# traning_shield.net
KiCad netlist of a schematic drawn in EAGLE
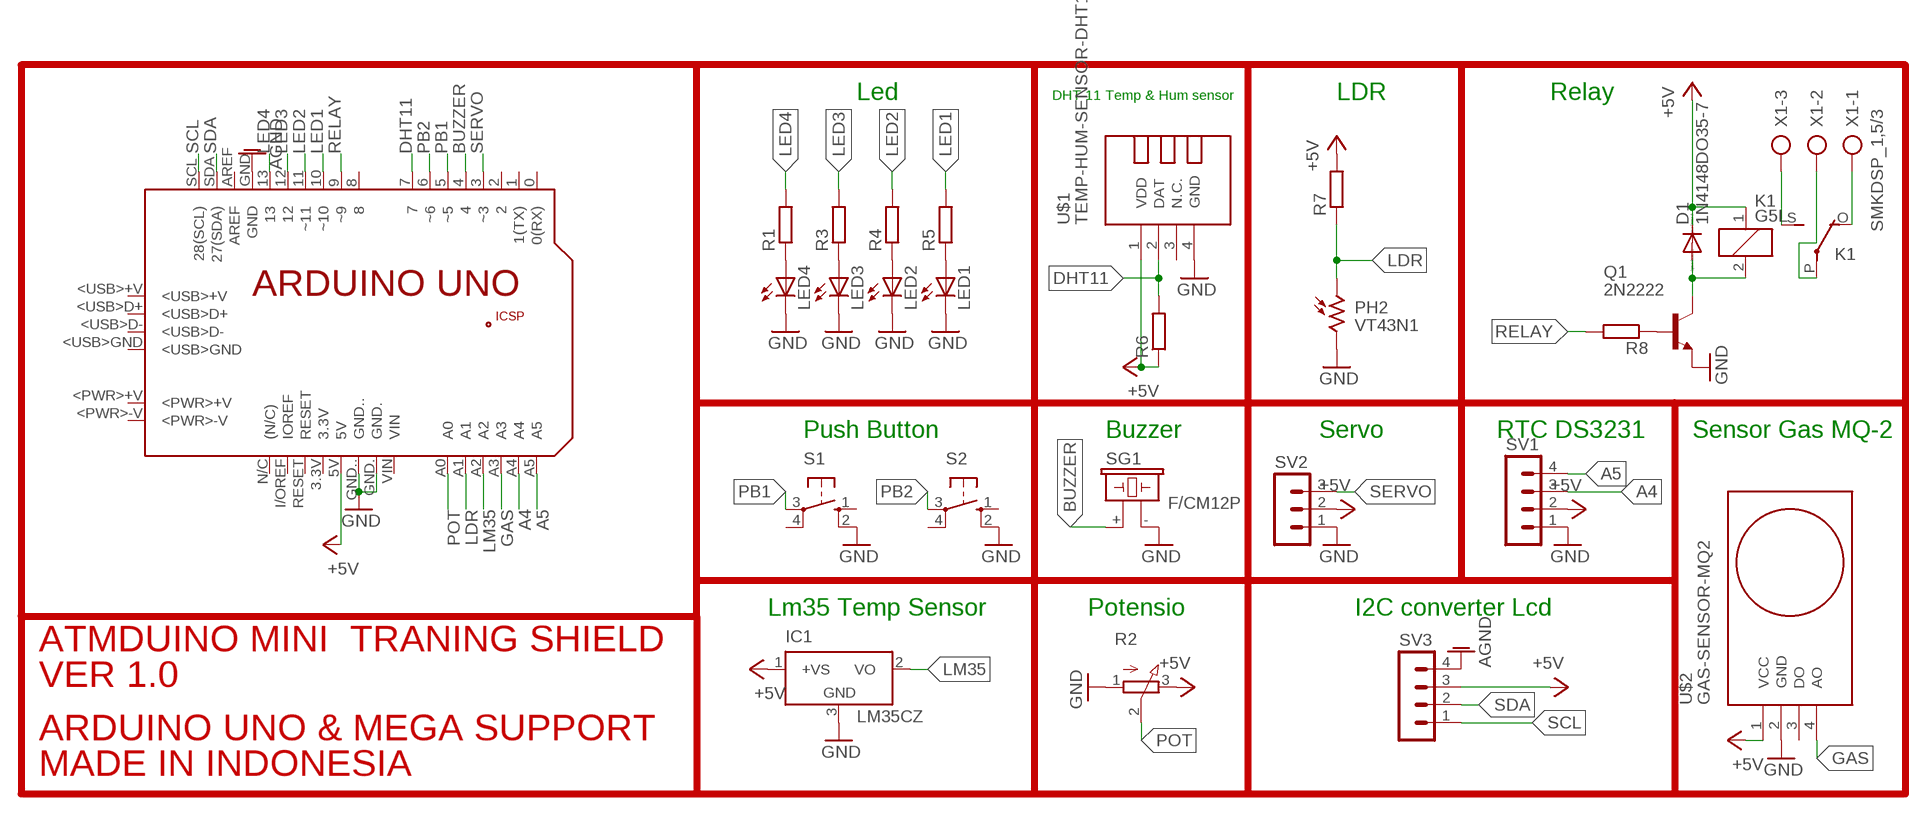
[diagram p0: schematic, sheet 1]

(export (version "E")
  (design (tool "Eeschema 10.0.6"))
  (components
    (comp (ref "D1")
      (value "1N4148DO35-7")
      (footprint "eagle-import:DO35-7")
      (libsource (lib "eagle-import") (part "1N4148DO35-7"))
    )
    (comp (ref "IC1")
      (value "LM35CZ")
      (footprint "eagle-import:TO92")
      (libsource (lib "eagle-import") (part "LM35CZ"))
    )
    (comp (ref "K1")
      (value "G5L")
      (footprint "eagle-import:G5LE")
      (libsource (lib "eagle-import") (part "G5L"))
    )
    (comp (ref "LED1")
      (value "LED5MM")
      (footprint "eagle-import:LED5MM")
      (libsource (lib "eagle-import") (part "LED5MM"))
    )
    (comp (ref "LED2")
      (value "LED5MM")
      (footprint "eagle-import:LED5MM")
      (libsource (lib "eagle-import") (part "LED5MM"))
    )
    (comp (ref "LED3")
      (value "LED5MM")
      (footprint "eagle-import:LED5MM")
      (libsource (lib "eagle-import") (part "LED5MM"))
    )
    (comp (ref "LED4")
      (value "LED5MM")
      (footprint "eagle-import:LED5MM")
      (libsource (lib "eagle-import") (part "LED5MM"))
    )
    (comp (ref "PCB1")
      (value "ARDUINO_UNO")
      (footprint "eagle-import:ARDUINO_UNO")
      (libsource (lib "eagle-import") (part "ARDUINO_UNO"))
    )
    (comp (ref "PH2")
      (value "VT43N1")
      (footprint "eagle-import:VT400")
      (libsource (lib "eagle-import") (part "VT43N1"))
    )
    (comp (ref "Q1")
      (value "2N2222")
      (footprint "eagle-import:TO18")
      (libsource (lib "eagle-import") (part "2N2222"))
    )
    (comp (ref "R1")
      (value "R-EU_0204/5")
      (footprint "eagle-import:0204_5")
      (libsource (lib "eagle-import") (part "R-EU_0204/5"))
    )
    (comp (ref "R2")
      (value "3RP/1610N")
      (footprint "eagle-import:3RP_1610N")
      (libsource (lib "eagle-import") (part "3RP/1610N"))
    )
    (comp (ref "R3")
      (value "R-EU_0204/5")
      (footprint "eagle-import:0204_5")
      (libsource (lib "eagle-import") (part "R-EU_0204/5"))
    )
    (comp (ref "R4")
      (value "R-EU_0204/5")
      (footprint "eagle-import:0204_5")
      (libsource (lib "eagle-import") (part "R-EU_0204/5"))
    )
    (comp (ref "R5")
      (value "R-EU_0204/5")
      (footprint "eagle-import:0204_5")
      (libsource (lib "eagle-import") (part "R-EU_0204/5"))
    )
    (comp (ref "R6")
      (value "R-EU_0204/5")
      (footprint "eagle-import:0204_5")
      (libsource (lib "eagle-import") (part "R-EU_0204/5"))
    )
    (comp (ref "R7")
      (value "R-EU_0204/5")
      (footprint "eagle-import:0204_5")
      (libsource (lib "eagle-import") (part "R-EU_0204/5"))
    )
    (comp (ref "R8")
      (value "R-EU_0204/5")
      (footprint "eagle-import:0204_5")
      (libsource (lib "eagle-import") (part "R-EU_0204/5"))
    )
    (comp (ref "S1")
      (value "10-XX")
      (footprint "eagle-import:B3F-10XX")
      (fields (field (name "MPN") "B3F-1000"))
      (libsource (lib "eagle-import") (part "10-XX"))
    )
    (comp (ref "S2")
      (value "10-XX")
      (footprint "eagle-import:B3F-10XX")
      (fields (field (name "MPN") "B3F-1000"))
      (libsource (lib "eagle-import") (part "10-XX"))
    )
    (comp (ref "SG1")
      (value "F/CM12P")
      (footprint "eagle-import:F_CM12P")
      (libsource (lib "eagle-import") (part "F/CM12P"))
    )
    (comp (ref "SV1")
      (value "MA04-1")
      (footprint "eagle-import:MA04-1")
      (libsource (lib "eagle-import") (part "MA04-1"))
    )
    (comp (ref "SV2")
      (value "MA03-1")
      (footprint "eagle-import:MA03-1")
      (libsource (lib "eagle-import") (part "MA03-1"))
    )
    (comp (ref "SV3")
      (value "MA04-1")
      (footprint "eagle-import:MA04-1")
      (libsource (lib "eagle-import") (part "MA04-1"))
    )
    (comp (ref "U$1")
      (value "TEMP-HUM-SENSOR-DHT11")
      (footprint "eagle-import:TEMP-HUM-SENSOR-DHT11")
      (libsource (lib "eagle-import") (part "TEMP-HUM-SENSOR-DHT11"))
    )
    (comp (ref "U$2")
      (value "GAS-SENSOR-MQ2")
      (footprint "eagle-import:GAS-SENSOR-MQ2")
      (libsource (lib "eagle-import") (part "GAS-SENSOR-MQ2"))
    )
    (comp (ref "X1")
      (value "SMKDSP_1,5/3")
      (footprint "eagle-import:SMKDSP_1,5_3")
      (fields (field (name "MF") "FARNELL") (field (name "MPN") "1733583"))
      (libsource (lib "eagle-import") (part "SMKDSP_1,5/3"))
    )
  )
  (nets
    (net (code "1") (name "+5V") (class "Default")
      (node (ref "D1") (pin "C") (pinfunction "C_C") (pintype "passive"))
      (node (ref "IC1") (pin "1") (pinfunction "+VS_1") (pintype "input"))
      (node (ref "K1") (pin "1") (pinfunction "1_1") (pintype "passive"))
      (node (ref "PCB1") (pin "5V") (pinfunction "5V_5V") (pintype "bidirectional"))
      (node (ref "R2") (pin "3") (pinfunction "E_3") (pintype "passive"))
      (node (ref "R6") (pin "1") (pinfunction "1_1") (pintype "passive"))
      (node (ref "R7") (pin "2") (pinfunction "2_2") (pintype "passive"))
      (node (ref "SV1") (pin "2") (pinfunction "2_2") (pintype "passive"))
      (node (ref "SV2") (pin "2") (pinfunction "2_2") (pintype "passive"))
      (node (ref "SV3") (pin "3") (pinfunction "3_3") (pintype "passive"))
      (node (ref "U$1") (pin "1") (pinfunction "VDD_1") (pintype "power_in"))
      (node (ref "U$2") (pin "1") (pinfunction "VCC_1") (pintype "power_in"))
    )
    (net (code "2") (name "A4") (class "Default")
      (node (ref "PCB1") (pin "A4") (pinfunction "A4_A4") (pintype "bidirectional"))
      (node (ref "SV1") (pin "3") (pinfunction "3_3") (pintype "passive"))
    )
    (net (code "3") (name "A5") (class "Default")
      (node (ref "PCB1") (pin "A5") (pinfunction "A5_A5") (pintype "bidirectional"))
      (node (ref "SV1") (pin "4") (pinfunction "4_4") (pintype "passive"))
    )
    (net (code "4") (name "AGND") (class "Default")
      (node (ref "PCB1") (pin "GND") (pinfunction "GND_GND") (pintype "bidirectional"))
      (node (ref "SV3") (pin "4") (pinfunction "4_4") (pintype "passive"))
    )
    (net (code "5") (name "BUZZER") (class "Default")
      (node (ref "PCB1") (pin "4") (pinfunction "4_4") (pintype "bidirectional"))
      (node (ref "SG1") (pin "+") (pinfunction "1_+") (pintype "passive"))
    )
    (net (code "6") (name "DHT11") (class "Default")
      (node (ref "PCB1") (pin "7") (pinfunction "7_7") (pintype "bidirectional"))
      (node (ref "R6") (pin "2") (pinfunction "2_2") (pintype "passive"))
      (node (ref "U$1") (pin "2") (pinfunction "DAT_2") (pintype "bidirectional"))
    )
    (net (code "7") (name "GAS") (class "Default")
      (node (ref "PCB1") (pin "A3") (pinfunction "A3_A3") (pintype "bidirectional"))
      (node (ref "U$2") (pin "4") (pinfunction "AO_4") (pintype "output"))
    )
    (net (code "8") (name "GND") (class "Default")
      (node (ref "IC1") (pin "3") (pinfunction "GND_3") (pintype "power_in"))
      (node (ref "LED1") (pin "K") (pinfunction "C_K") (pintype "passive"))
      (node (ref "LED2") (pin "K") (pinfunction "C_K") (pintype "passive"))
      (node (ref "LED3") (pin "K") (pinfunction "C_K") (pintype "passive"))
      (node (ref "LED4") (pin "K") (pinfunction "C_K") (pintype "passive"))
      (node (ref "PCB1") (pin "GND.") (pinfunction "GND._GND.") (pintype "bidirectional"))
      (node (ref "PCB1") (pin "GND..") (pinfunction "GND.._GND..") (pintype "bidirectional"))
      (node (ref "PH2") (pin "2") (pinfunction "2_2") (pintype "passive"))
      (node (ref "Q1") (pin "1") (pinfunction "E_1") (pintype "passive"))
      (node (ref "R2") (pin "1") (pinfunction "A_1") (pintype "passive"))
      (node (ref "S1") (pin "2") (pinfunction "S1_2") (pintype "passive"))
      (node (ref "S2") (pin "2") (pinfunction "S1_2") (pintype "passive"))
      (node (ref "SG1") (pin "-") (pinfunction "2_-") (pintype "passive"))
      (node (ref "SV1") (pin "1") (pinfunction "1_1") (pintype "passive"))
      (node (ref "SV2") (pin "1") (pinfunction "1_1") (pintype "passive"))
      (node (ref "U$1") (pin "4") (pinfunction "GND_4") (pintype "power_in"))
      (node (ref "U$2") (pin "2") (pinfunction "GND_2") (pintype "power_in"))
    )
    (net (code "9") (name "LDR") (class "Default")
      (node (ref "PCB1") (pin "A1") (pinfunction "A1_A1") (pintype "bidirectional"))
      (node (ref "PH2") (pin "1") (pinfunction "1_1") (pintype "passive"))
      (node (ref "R7") (pin "1") (pinfunction "1_1") (pintype "passive"))
    )
    (net (code "10") (name "LED1") (class "Default")
      (node (ref "PCB1") (pin "10") (pinfunction "~{10}_10") (pintype "bidirectional"))
      (node (ref "R5") (pin "2") (pinfunction "2_2") (pintype "passive"))
    )
    (net (code "11") (name "LED2") (class "Default")
      (node (ref "PCB1") (pin "11") (pinfunction "~{11}_11") (pintype "bidirectional"))
      (node (ref "R4") (pin "2") (pinfunction "2_2") (pintype "passive"))
    )
    (net (code "12") (name "LED3") (class "Default")
      (node (ref "PCB1") (pin "12") (pinfunction "12_12") (pintype "bidirectional"))
      (node (ref "R3") (pin "2") (pinfunction "2_2") (pintype "passive"))
    )
    (net (code "13") (name "LED4") (class "Default")
      (node (ref "PCB1") (pin "13") (pinfunction "13_13") (pintype "bidirectional"))
      (node (ref "R1") (pin "2") (pinfunction "2_2") (pintype "passive"))
    )
    (net (code "14") (name "LM35") (class "Default")
      (node (ref "IC1") (pin "2") (pinfunction "VO_2") (pintype "input"))
      (node (ref "PCB1") (pin "A2") (pinfunction "A2_A2") (pintype "bidirectional"))
    )
    (net (code "15") (name "Net-(LED1-PadA)") (class "Default")
      (node (ref "LED1") (pin "A") (pinfunction "A_A") (pintype "passive"))
      (node (ref "R5") (pin "1") (pinfunction "1_1") (pintype "passive"))
    )
    (net (code "16") (name "Net-(LED2-PadA)") (class "Default")
      (node (ref "LED2") (pin "A") (pinfunction "A_A") (pintype "passive"))
      (node (ref "R4") (pin "1") (pinfunction "1_1") (pintype "passive"))
    )
    (net (code "17") (name "Net-(LED3-PadA)") (class "Default")
      (node (ref "LED3") (pin "A") (pinfunction "A_A") (pintype "passive"))
      (node (ref "R3") (pin "1") (pinfunction "1_1") (pintype "passive"))
    )
    (net (code "18") (name "Net-(LED4-PadA)") (class "Default")
      (node (ref "LED4") (pin "A") (pinfunction "A_A") (pintype "passive"))
      (node (ref "R1") (pin "1") (pinfunction "1_1") (pintype "passive"))
    )
    (net (code "19") (name "Net-(Q1-B)") (class "Default")
      (node (ref "Q1") (pin "2") (pinfunction "B_2") (pintype "passive"))
      (node (ref "R8") (pin "1") (pinfunction "1_1") (pintype "passive"))
    )
    (net (code "20") (name "Net-(Q1-C)") (class "Default")
      (node (ref "D1") (pin "A") (pinfunction "A_A") (pintype "passive"))
      (node (ref "K1") (pin "2") (pinfunction "2_2") (pintype "passive"))
      (node (ref "Q1") (pin "3") (pinfunction "C_3") (pintype "passive"))
    )
    (net (code "21") (name "Net-(X1A-KL)") (class "Default")
      (node (ref "K1") (pin "O") (pinfunction "O_O") (pintype "passive"))
      (node (ref "X1") (pin "1") (pinfunction "KL_1") (pintype "passive"))
    )
    (net (code "22") (name "Net-(X1B-KL)") (class "Default")
      (node (ref "K1") (pin "P") (pinfunction "P_P") (pintype "passive"))
      (node (ref "X1") (pin "2") (pinfunction "KL_2") (pintype "passive"))
    )
    (net (code "23") (name "Net-(X1C-KL)") (class "Default")
      (node (ref "K1") (pin "S") (pinfunction "S_S") (pintype "passive"))
      (node (ref "X1") (pin "3") (pinfunction "KL_3") (pintype "passive"))
    )
    (net (code "24") (name "PB1") (class "Default")
      (node (ref "PCB1") (pin "5") (pinfunction "~{5}_5") (pintype "bidirectional"))
      (node (ref "S1") (pin "3") (pinfunction "P_3") (pintype "passive"))
    )
    (net (code "25") (name "PB2") (class "Default")
      (node (ref "PCB1") (pin "6") (pinfunction "~{6}_6") (pintype "bidirectional"))
      (node (ref "S2") (pin "3") (pinfunction "P_3") (pintype "passive"))
    )
    (net (code "26") (name "POT") (class "Default")
      (node (ref "PCB1") (pin "A0") (pinfunction "A0_A0") (pintype "bidirectional"))
      (node (ref "R2") (pin "2") (pinfunction "S_2") (pintype "passive"))
    )
    (net (code "27") (name "RELAY") (class "Default")
      (node (ref "PCB1") (pin "9") (pinfunction "~{9}_9") (pintype "bidirectional"))
      (node (ref "R8") (pin "2") (pinfunction "2_2") (pintype "passive"))
    )
    (net (code "28") (name "SCL") (class "Default")
      (node (ref "PCB1") (pin "SCL") (pinfunction "28(SCL)_SCL") (pintype "bidirectional"))
      (node (ref "SV3") (pin "1") (pinfunction "1_1") (pintype "passive"))
    )
    (net (code "29") (name "SDA") (class "Default")
      (node (ref "PCB1") (pin "SDA") (pinfunction "27(SDA)_SDA") (pintype "bidirectional"))
      (node (ref "SV3") (pin "2") (pinfunction "2_2") (pintype "passive"))
    )
    (net (code "30") (name "SERVO") (class "Default")
      (node (ref "PCB1") (pin "3") (pinfunction "~{3}_3") (pintype "bidirectional"))
      (node (ref "SV2") (pin "3") (pinfunction "3_3") (pintype "passive"))
    )
    (net (code "31") (name "unconnected-(PCB1-(N{slash}C)-PadN{slash}C)") (class "Default")
      (node (ref "PCB1") (pin "N/C") (pinfunction "(N/C)_N/C") (pintype "bidirectional"))
    )
    (net (code "32") (name "unconnected-(PCB1-0(RX)-Pad0)") (class "Default")
      (node (ref "PCB1") (pin "0") (pinfunction "0(RX)_0") (pintype "bidirectional"))
    )
    (net (code "33") (name "unconnected-(PCB1-1(TX)-Pad1)") (class "Default")
      (node (ref "PCB1") (pin "1") (pinfunction "1(TX)_1") (pintype "bidirectional"))
    )
    (net (code "34") (name "unconnected-(PCB1-IOREF-PadI{slash}OREF)") (class "Default")
      (node (ref "PCB1") (pin "I/OREF") (pinfunction "IOREF_I/OREF") (pintype "bidirectional"))
    )
    (net (code "35") (name "unconnected-(PCB1-Pad+5V)") (class "Default")
      (node (ref "PCB1") (pin "+5V") (pinfunction "+5V_+5V") (pintype "bidirectional"))
    )
    (net (code "36") (name "unconnected-(PCB1-Pad2)") (class "Default")
      (node (ref "PCB1") (pin "2") (pinfunction "2_2") (pintype "bidirectional"))
    )
    (net (code "37") (name "unconnected-(PCB1-Pad3.3V)") (class "Default")
      (node (ref "PCB1") (pin "3.3V") (pinfunction "3.3V_3.3V") (pintype "bidirectional"))
    )
    (net (code "38") (name "unconnected-(PCB1-Pad8)") (class "Default")
      (node (ref "PCB1") (pin "8") (pinfunction "8_8") (pintype "bidirectional"))
    )
    (net (code "39") (name "unconnected-(PCB1-Pad<PWR>+V)") (class "Default")
      (node (ref "PCB1") (pin "<PWR>+V") (pinfunction "<PWR>+V_<PWR>+V") (pintype "bidirectional"))
    )
    (net (code "40") (name "unconnected-(PCB1-Pad<PWR>-V)") (class "Default")
      (node (ref "PCB1") (pin "<PWR>-V") (pinfunction "<PWR>-V_<PWR>-V") (pintype "bidirectional"))
    )
    (net (code "41") (name "unconnected-(PCB1-Pad<USB>+V)") (class "Default")
      (node (ref "PCB1") (pin "<USB>+V") (pinfunction "<USB>+V_<USB>+V") (pintype "bidirectional"))
    )
    (net (code "42") (name "unconnected-(PCB1-Pad<USB>D+)") (class "Default")
      (node (ref "PCB1") (pin "<USB>D+") (pinfunction "<USB>D+_<USB>D+") (pintype "bidirectional"))
    )
    (net (code "43") (name "unconnected-(PCB1-Pad<USB>D-)") (class "Default")
      (node (ref "PCB1") (pin "<USB>D-") (pinfunction "<USB>D-_<USB>D-") (pintype "bidirectional"))
    )
    (net (code "44") (name "unconnected-(PCB1-Pad<USB>GND)") (class "Default")
      (node (ref "PCB1") (pin "<USB>GND") (pinfunction "<USB>GND_<USB>GND") (pintype "bidirectional"))
    )
    (net (code "45") (name "unconnected-(PCB1-PadAREF)") (class "Default")
      (node (ref "PCB1") (pin "AREF") (pinfunction "AREF_AREF") (pintype "bidirectional"))
    )
    (net (code "46") (name "unconnected-(PCB1-PadGND_)") (class "Default")
      (node (ref "PCB1") (pin "GND_") (pinfunction "GND__GND_") (pintype "bidirectional"))
    )
    (net (code "47") (name "unconnected-(PCB1-PadMISO)") (class "Default")
      (node (ref "PCB1") (pin "MISO") (pinfunction "MISO_MISO") (pintype "bidirectional"))
    )
    (net (code "48") (name "unconnected-(PCB1-PadMOSI)") (class "Default")
      (node (ref "PCB1") (pin "MOSI") (pinfunction "MOSI_MOSI") (pintype "bidirectional"))
    )
    (net (code "49") (name "unconnected-(PCB1-PadRESET)") (class "Default")
      (node (ref "PCB1") (pin "RESET") (pinfunction "RESET_RESET") (pintype "bidirectional"))
    )
    (net (code "50") (name "unconnected-(PCB1-PadRESET.)") (class "Default")
      (node (ref "PCB1") (pin "RESET.") (pinfunction "RESET._RESET.") (pintype "bidirectional"))
    )
    (net (code "51") (name "unconnected-(PCB1-PadSCK)") (class "Default")
      (node (ref "PCB1") (pin "SCK") (pinfunction "SCK_SCK") (pintype "bidirectional"))
    )
    (net (code "52") (name "unconnected-(PCB1-PadVIN)") (class "Default")
      (node (ref "PCB1") (pin "VIN") (pinfunction "VIN_VIN") (pintype "bidirectional"))
    )
    (net (code "53") (name "unconnected-(S1-P1-Pad4)") (class "Default")
      (node (ref "S1") (pin "4") (pinfunction "P1_4") (pintype "passive"))
    )
    (net (code "54") (name "unconnected-(S1-S-Pad1)") (class "Default")
      (node (ref "S1") (pin "1") (pinfunction "S_1") (pintype "passive"))
    )
    (net (code "55") (name "unconnected-(S2-P1-Pad4)") (class "Default")
      (node (ref "S2") (pin "4") (pinfunction "P1_4") (pintype "passive"))
    )
    (net (code "56") (name "unconnected-(S2-S-Pad1)") (class "Default")
      (node (ref "S2") (pin "1") (pinfunction "S_1") (pintype "passive"))
    )
    (net (code "57") (name "unconnected-(U$1-N.C.-Pad3)") (class "Default")
      (node (ref "U$1") (pin "3") (pinfunction "N.C._3") (pintype "passive"))
    )
    (net (code "58") (name "unconnected-(U$2-DO-Pad3)") (class "Default")
      (node (ref "U$2") (pin "3") (pinfunction "DO_3") (pintype "output"))
    )
  )
)
